# main_board.net
KiCad netlist of a schematic drawn in EAGLE
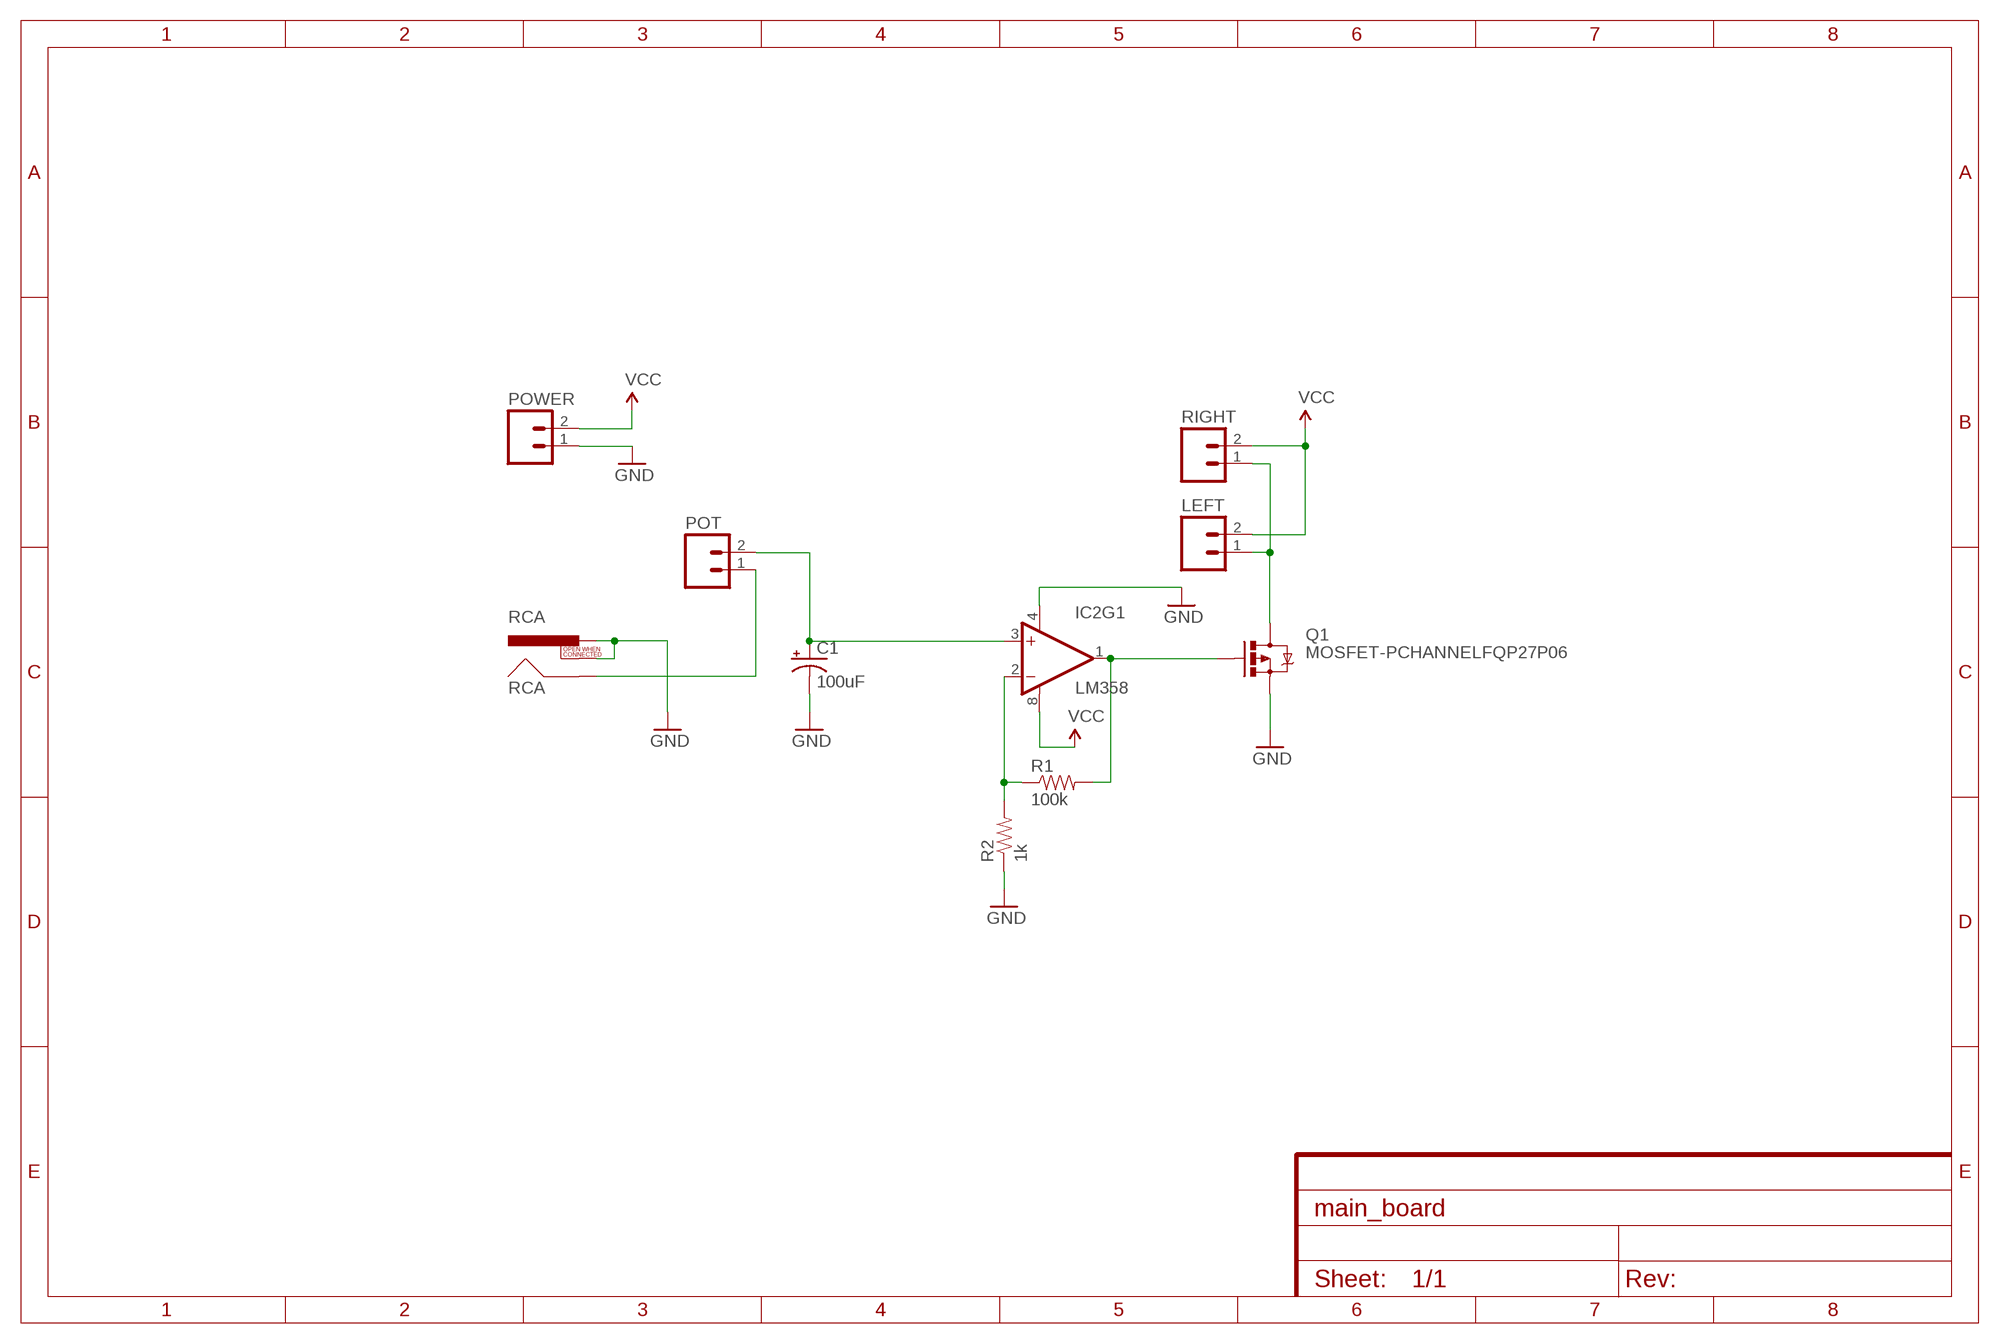
[diagram p0: schematic, sheet 1]

(export (version "E")
  (design (tool "Eeschema 10.0.6"))
  (components
    (comp (ref "C1")
      (value "100uF")
      (footprint "eagle-import:CPOL-RADIAL-100UF-25V")
      (libsource (lib "eagle-import") (part "CAP_POLPTH1"))
    )
    (comp (ref "IC2")
      (value "LM358")
      (footprint "eagle-import:DIP08")
      (libsource (lib "eagle-import") (part "LM358"))
    )
    (comp (ref "LEFT")
      (value "M02PTH")
      (footprint "eagle-import:1X02")
      (libsource (lib "eagle-import") (part "M02PTH"))
    )
    (comp (ref "POT")
      (value "M02PTH")
      (footprint "eagle-import:1X02")
      (libsource (lib "eagle-import") (part "M02PTH"))
    )
    (comp (ref "POWER")
      (value "M02PTH")
      (footprint "eagle-import:1X02")
      (libsource (lib "eagle-import") (part "M02PTH"))
    )
    (comp (ref "Q1")
      (value "MOSFET-PCHANNELFQP27P06")
      (footprint "eagle-import:TO220V")
      (libsource (lib "eagle-import") (part "MOSFET-PCHANNELFQP27P06"))
    )
    (comp (ref "R1")
      (value "100k")
      (footprint "eagle-import:AXIAL-0.3-KIT")
      (libsource (lib "eagle-import") (part "RESISTORKIT"))
    )
    (comp (ref "R2")
      (value "1k")
      (footprint "eagle-import:AXIAL-0.3-KIT")
      (libsource (lib "eagle-import") (part "RESISTORKIT"))
    )
    (comp (ref "RCA")
      (value "RCA")
      (footprint "eagle-import:RCA")
      (libsource (lib "eagle-import") (part "RCA"))
    )
    (comp (ref "RIGHT")
      (value "M02PTH")
      (footprint "eagle-import:1X02")
      (libsource (lib "eagle-import") (part "M02PTH"))
    )
  )
  (nets
    (net (code "1") (name "GND") (class "Default")
      (node (ref "C1") (pin "2") (pinfunction "-_2") (pintype "passive"))
      (node (ref "IC2") (pin "4") (pinfunction "V-_4") (pintype "power_in"))
      (node (ref "POWER") (pin "1") (pinfunction "1_1") (pintype "passive"))
      (node (ref "Q1") (pin "3") (pinfunction "S_3") (pintype "passive"))
      (node (ref "R2") (pin "P$1") (pinfunction "1_P$1") (pintype "passive"))
      (node (ref "RCA") (pin "PIN") (pinfunction "PIN_PIN") (pintype "bidirectional"))
      (node (ref "RCA") (pin "SWITCH") (pinfunction "SWITCH_SWITCH") (pintype "bidirectional"))
    )
    (net (code "2") (name "Net-(C1-+)") (class "Default")
      (node (ref "C1") (pin "1") (pinfunction "+_1") (pintype "passive"))
      (node (ref "IC2") (pin "3") (pinfunction "+IN_3") (pintype "input"))
      (node (ref "POT") (pin "2") (pinfunction "2_2") (pintype "passive"))
    )
    (net (code "3") (name "Net-(IC2A--IN)") (class "Default")
      (node (ref "IC2") (pin "2") (pinfunction "-IN_2") (pintype "input"))
      (node (ref "R1") (pin "P$1") (pinfunction "1_P$1") (pintype "passive"))
      (node (ref "R2") (pin "P$2") (pinfunction "2_P$2") (pintype "passive"))
    )
    (net (code "4") (name "Net-(IC2A-OUT)") (class "Default")
      (node (ref "IC2") (pin "1") (pinfunction "OUT_1") (pintype "output"))
      (node (ref "Q1") (pin "1") (pinfunction "G_1") (pintype "passive"))
      (node (ref "R1") (pin "P$2") (pinfunction "2_P$2") (pintype "passive"))
    )
    (net (code "5") (name "Net-(POT-Pad1)") (class "Default")
      (node (ref "POT") (pin "1") (pinfunction "1_1") (pintype "passive"))
      (node (ref "RCA") (pin "SHELL") (pinfunction "SHELL_SHELL") (pintype "bidirectional"))
    )
    (net (code "6") (name "Net-(Q1-D)") (class "Default")
      (node (ref "LEFT") (pin "1") (pinfunction "1_1") (pintype "passive"))
      (node (ref "Q1") (pin "2") (pinfunction "D_2") (pintype "passive"))
      (node (ref "RIGHT") (pin "1") (pinfunction "1_1") (pintype "passive"))
    )
    (net (code "7") (name "VCC") (class "Default")
      (node (ref "IC2") (pin "8") (pinfunction "V+_8") (pintype "power_in"))
      (node (ref "LEFT") (pin "2") (pinfunction "2_2") (pintype "passive"))
      (node (ref "POWER") (pin "2") (pinfunction "2_2") (pintype "passive"))
      (node (ref "RIGHT") (pin "2") (pinfunction "2_2") (pintype "passive"))
    )
  )
)
